# MCU.net
KiCad netlist of a schematic drawn in Altium Designer
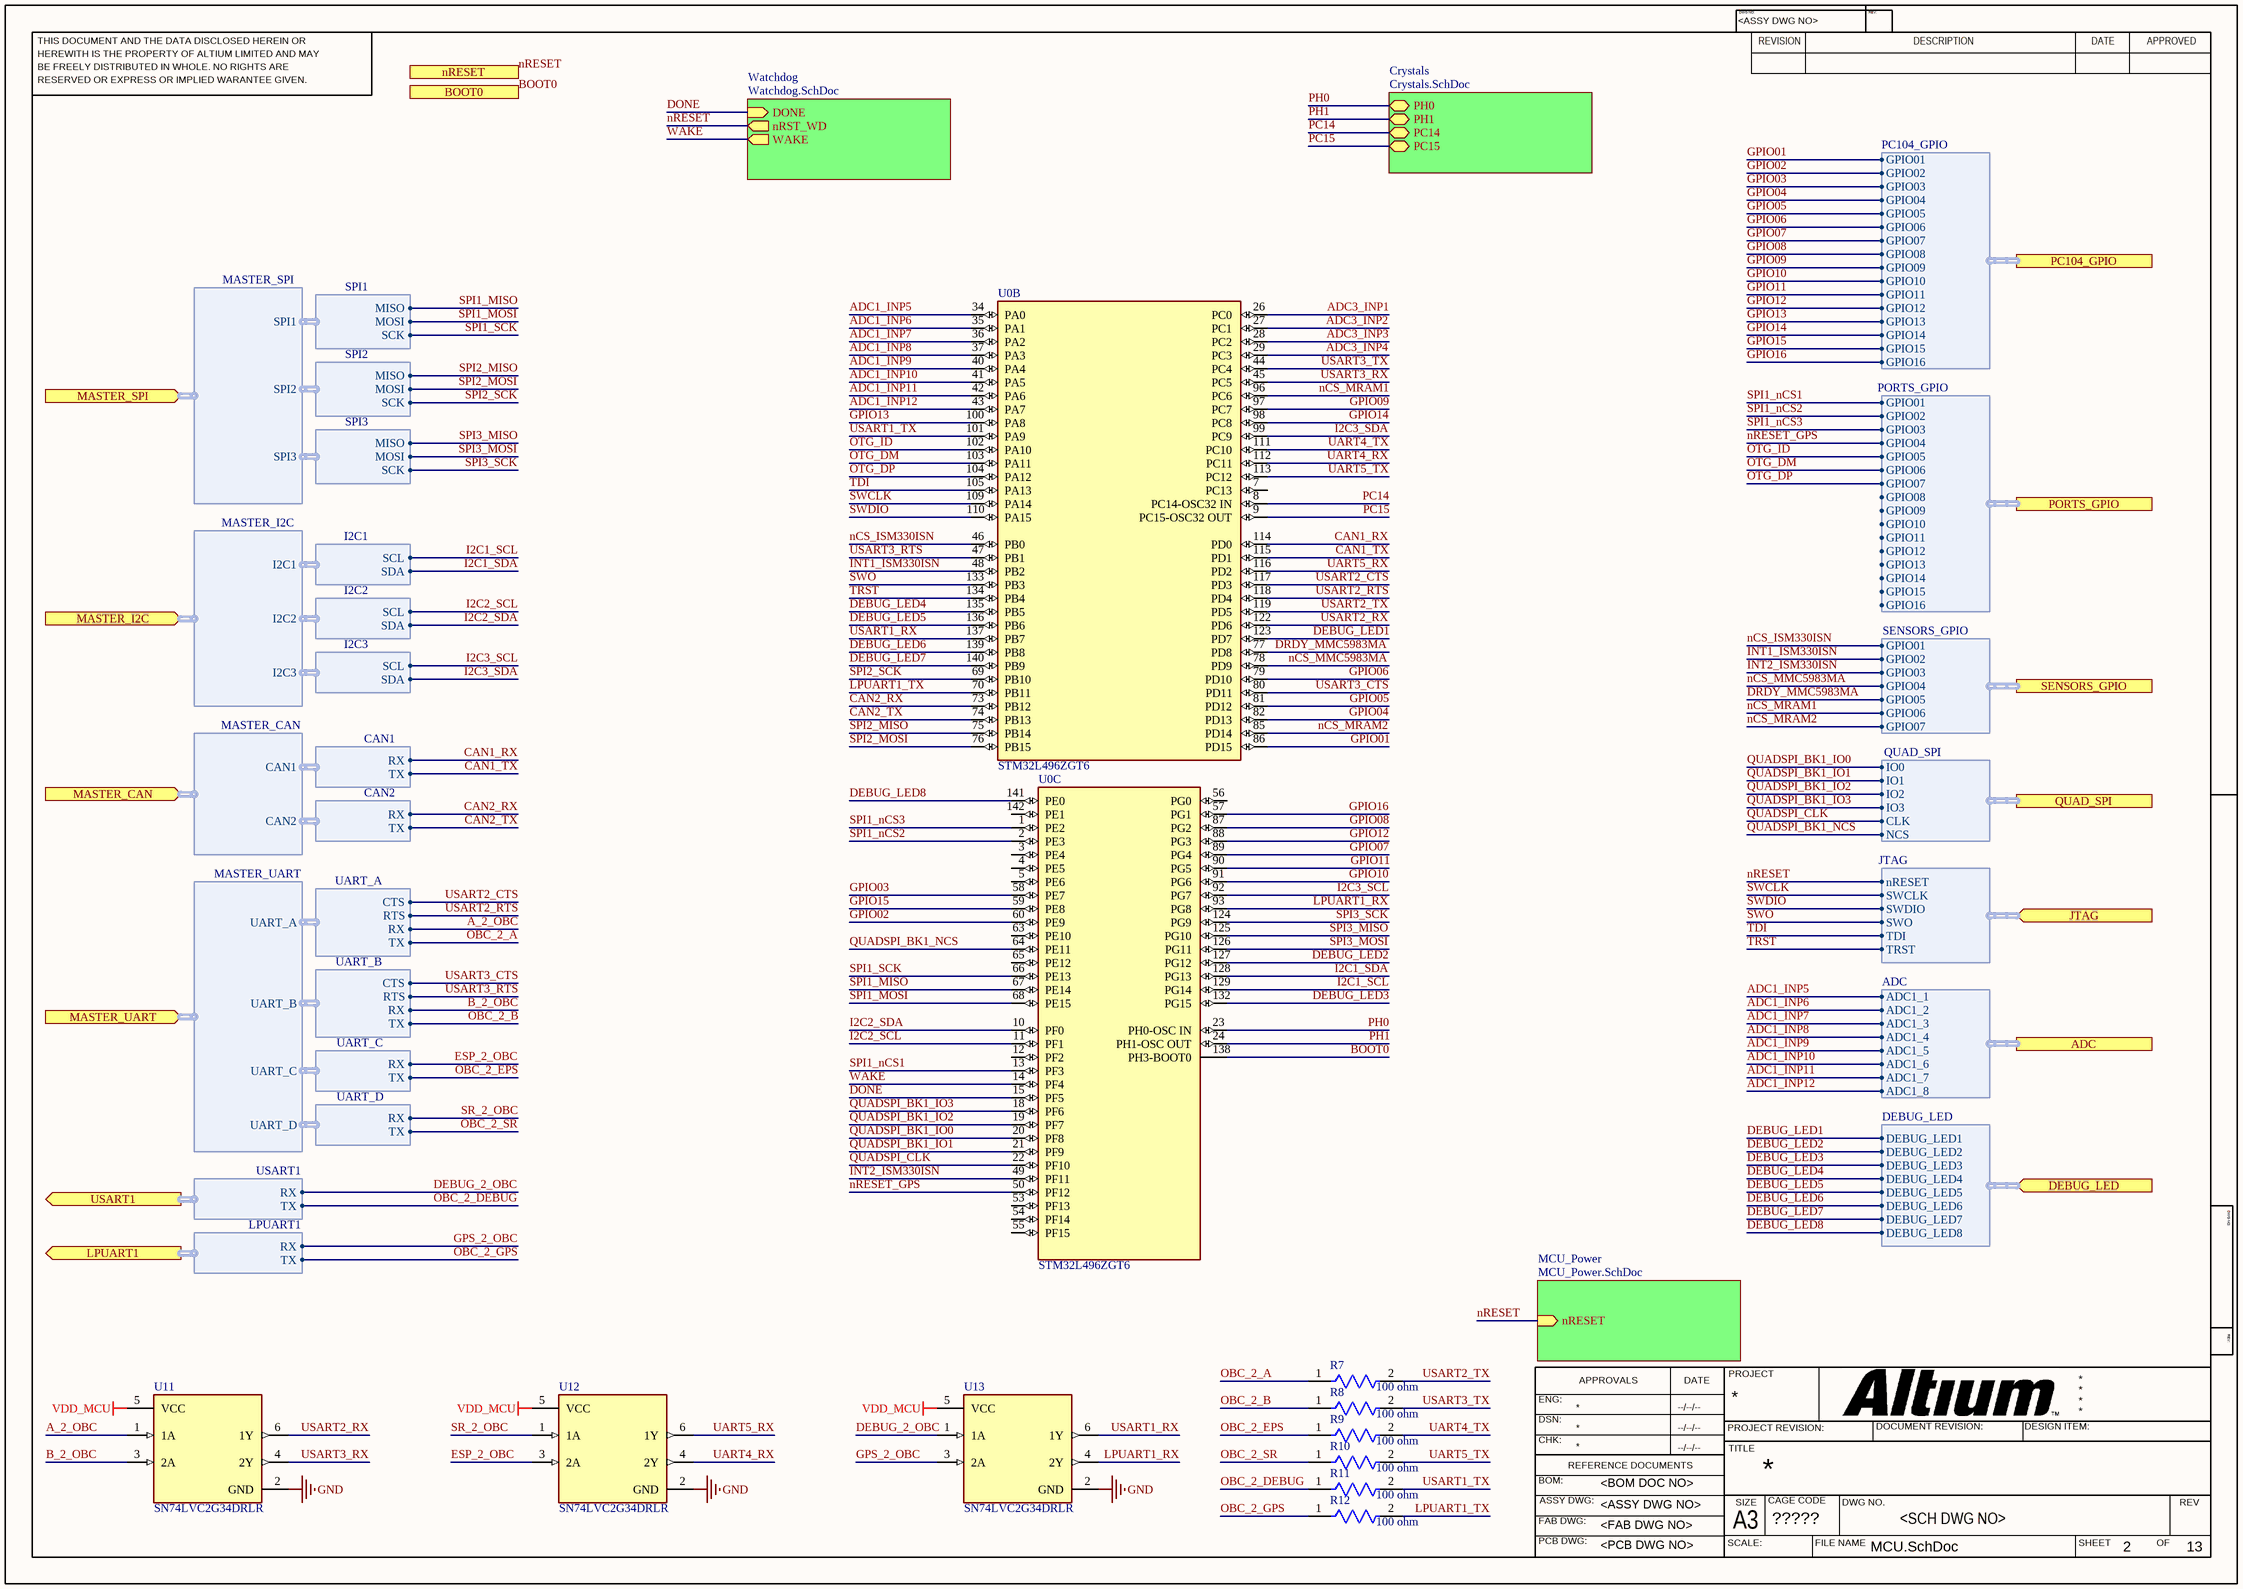
[diagram p0: MCU.SchDoc]

(export (version "E")
  (design (tool "Eeschema 10.0.6"))
  (components
    (comp (ref "R7")
      (value "100 ohm")
      (footprint "FP-ERJP03-MFG")
      (description "ERJ-P03F1000V SMD Chip Resistor, 100 Ohm, ± 1%, 200 mW, 0603 [1608 Metric], Thick Film, Anti-Surge")
      (fields (field (name "TOLERANCE") "1%"))
      (libsource (lib "Altium Content Vault") (part "1029c3af85768c4190bb7ad29bc67b5"))
    )
    (comp (ref "R8")
      (value "100 ohm")
      (footprint "FP-ERJP03-MFG")
      (description "ERJ-P03F1000V SMD Chip Resistor, 100 Ohm, ± 1%, 200 mW, 0603 [1608 Metric], Thick Film, Anti-Surge")
      (fields (field (name "TOLERANCE") "1%"))
      (libsource (lib "Altium Content Vault") (part "1029c3af85768c4190bb7ad29bc67b5"))
    )
    (comp (ref "R9")
      (value "100 ohm")
      (footprint "FP-ERJP03-MFG")
      (description "ERJ-P03F1000V SMD Chip Resistor, 100 Ohm, ± 1%, 200 mW, 0603 [1608 Metric], Thick Film, Anti-Surge")
      (fields (field (name "TOLERANCE") "1%"))
      (libsource (lib "Altium Content Vault") (part "1029c3af85768c4190bb7ad29bc67b5"))
    )
    (comp (ref "R10")
      (value "100 ohm")
      (footprint "FP-ERJP03-MFG")
      (description "ERJ-P03F1000V SMD Chip Resistor, 100 Ohm, ± 1%, 200 mW, 0603 [1608 Metric], Thick Film, Anti-Surge")
      (fields (field (name "TOLERANCE") "1%"))
      (libsource (lib "Altium Content Vault") (part "1029c3af85768c4190bb7ad29bc67b5"))
    )
    (comp (ref "R11")
      (value "100 ohm")
      (footprint "FP-ERJP03-MFG")
      (description "ERJ-P03F1000V SMD Chip Resistor, 100 Ohm, ± 1%, 200 mW, 0603 [1608 Metric], Thick Film, Anti-Surge")
      (fields (field (name "TOLERANCE") "1%"))
      (libsource (lib "Altium Content Vault") (part "1029c3af85768c4190bb7ad29bc67b5"))
    )
    (comp (ref "R12")
      (value "100 ohm")
      (footprint "FP-ERJP03-MFG")
      (description "ERJ-P03F1000V SMD Chip Resistor, 100 Ohm, ± 1%, 200 mW, 0603 [1608 Metric], Thick Film, Anti-Surge")
      (fields (field (name "TOLERANCE") "1%"))
      (libsource (lib "Altium Content Vault") (part "1029c3af85768c4190bb7ad29bc67b5"))
    )
    (comp (ref "U0")
      (value "STM32L496ZGT6")
      (footprint "FP-LQFP144-1A-MFG")
      (description "IC MCU 32BIT 1MB FLASH 144LQFP")
      (libsource (lib "Altium Content Vault") (part "f8f598a4e7bf6abd6ff1d35fb83b48f"))
    )
    (comp (ref "U11")
      (value "SN74LVC2G34DRLR")
      (footprint "FP-DRL0006A-MFG")
      (description "IC BUFFER NON-INVERT 5.5V 6SOT")
      (libsource (lib "Altium Content Vault") (part "59303bce76f5fafbc101ba271662c75"))
    )
    (comp (ref "U12")
      (value "SN74LVC2G34DRLR")
      (footprint "FP-DRL0006A-MFG")
      (description "IC BUFFER NON-INVERT 5.5V 6SOT")
      (libsource (lib "Altium Content Vault") (part "59303bce76f5fafbc101ba271662c75"))
    )
    (comp (ref "U13")
      (value "SN74LVC2G34DRLR")
      (footprint "FP-DRL0006A-MFG")
      (description "IC BUFFER NON-INVERT 5.5V 6SOT")
      (libsource (lib "Altium Content Vault") (part "59303bce76f5fafbc101ba271662c75"))
    )
  )
  (nets
    (net (code "26") (name "/ADC1_INP5") (class "Default")
      (node (ref "U0") (pin "34") (pinfunction "PA0_34") (pintype "bidirectional"))
    )
    (net (code "27") (name "/ADC1_INP6") (class "Default")
      (node (ref "U0") (pin "35") (pinfunction "PA1_35") (pintype "bidirectional"))
    )
    (net (code "28") (name "/ADC1_INP7") (class "Default")
      (node (ref "U0") (pin "36") (pinfunction "PA2_36") (pintype "bidirectional"))
    )
    (net (code "29") (name "/ADC1_INP8") (class "Default")
      (node (ref "U0") (pin "37") (pinfunction "PA3_37") (pintype "bidirectional"))
    )
    (net (code "30") (name "/ADC1_INP9") (class "Default")
      (node (ref "U0") (pin "40") (pinfunction "PA4_40") (pintype "bidirectional"))
    )
    (net (code "31") (name "/ADC1_INP10") (class "Default")
      (node (ref "U0") (pin "41") (pinfunction "PA5_41") (pintype "bidirectional"))
    )
    (net (code "32") (name "/ADC1_INP11") (class "Default")
      (node (ref "U0") (pin "42") (pinfunction "PA6_42") (pintype "bidirectional"))
    )
    (net (code "33") (name "/ADC1_INP12") (class "Default")
      (node (ref "U0") (pin "43") (pinfunction "PA7_43") (pintype "bidirectional"))
    )
    (net (code "34") (name "/ADC3_INP1") (class "Default")
      (node (ref "U0") (pin "26") (pinfunction "PC0_26") (pintype "bidirectional"))
    )
    (net (code "35") (name "/ADC3_INP2") (class "Default")
      (node (ref "U0") (pin "27") (pinfunction "PC1_27") (pintype "bidirectional"))
    )
    (net (code "36") (name "/ADC3_INP3") (class "Default")
      (node (ref "U0") (pin "28") (pinfunction "PC2_28") (pintype "bidirectional"))
    )
    (net (code "37") (name "/ADC3_INP4") (class "Default")
      (node (ref "U0") (pin "29") (pinfunction "PC3_29") (pintype "bidirectional"))
    )
    (net (code "38") (name "/A_2_OBC") (class "Default")
      (node (ref "U11") (pin "1") (pinfunction "1A_1") (pintype "input"))
    )
    (net (code "39") (name "/BOOT0") (class "Default")
      (node (ref "U0") (pin "138") (pinfunction "PH3-BOOT0_138") (pintype "passive"))
    )
    (net (code "40") (name "/B_2_OBC") (class "Default")
      (node (ref "U11") (pin "3") (pinfunction "2A_3") (pintype "input"))
    )
    (net (code "41") (name "/CAN1_RX") (class "Default")
      (node (ref "U0") (pin "114") (pinfunction "PD0_114") (pintype "bidirectional"))
    )
    (net (code "42") (name "/CAN1_TX") (class "Default")
      (node (ref "U0") (pin "115") (pinfunction "PD1_115") (pintype "bidirectional"))
    )
    (net (code "43") (name "/CAN2_RX") (class "Default")
      (node (ref "U0") (pin "73") (pinfunction "PB12_73") (pintype "bidirectional"))
    )
    (net (code "44") (name "/CAN2_TX") (class "Default")
      (node (ref "U0") (pin "74") (pinfunction "PB13_74") (pintype "bidirectional"))
    )
    (net (code "45") (name "/DEBUG_2_OBC") (class "Default")
      (node (ref "U13") (pin "1") (pinfunction "1A_1") (pintype "input"))
    )
    (net (code "46") (name "/DEBUG_LED1") (class "Default")
      (node (ref "U0") (pin "123") (pinfunction "PD7_123") (pintype "bidirectional"))
    )
    (net (code "47") (name "/DEBUG_LED2") (class "Default")
      (node (ref "U0") (pin "127") (pinfunction "PG12_127") (pintype "bidirectional"))
    )
    (net (code "48") (name "/DEBUG_LED3") (class "Default")
      (node (ref "U0") (pin "132") (pinfunction "PG15_132") (pintype "bidirectional"))
    )
    (net (code "49") (name "/DEBUG_LED4") (class "Default")
      (node (ref "U0") (pin "135") (pinfunction "PB5_135") (pintype "bidirectional"))
    )
    (net (code "50") (name "/DEBUG_LED5") (class "Default")
      (node (ref "U0") (pin "136") (pinfunction "PB6_136") (pintype "bidirectional"))
    )
    (net (code "51") (name "/DEBUG_LED6") (class "Default")
      (node (ref "U0") (pin "139") (pinfunction "PB8_139") (pintype "bidirectional"))
    )
    (net (code "52") (name "/DEBUG_LED7") (class "Default")
      (node (ref "U0") (pin "140") (pinfunction "PB9_140") (pintype "bidirectional"))
    )
    (net (code "53") (name "/DEBUG_LED8") (class "Default")
      (node (ref "U0") (pin "141") (pinfunction "PE0_141") (pintype "bidirectional"))
    )
    (net (code "54") (name "/DONE") (class "Default")
      (node (ref "U0") (pin "15") (pinfunction "PF5_15") (pintype "bidirectional"))
    )
    (net (code "55") (name "/DRDY_MMC5983MA") (class "Default")
      (node (ref "U0") (pin "77") (pinfunction "PD8_77") (pintype "bidirectional"))
    )
    (net (code "56") (name "/ESP_2_OBC") (class "Default")
      (node (ref "U12") (pin "3") (pinfunction "2A_3") (pintype "input"))
    )
    (net (code "57") (name "/GPIO01") (class "Default")
      (node (ref "U0") (pin "86") (pinfunction "PD15_86") (pintype "bidirectional"))
    )
    (net (code "58") (name "/GPIO02") (class "Default")
      (node (ref "U0") (pin "60") (pinfunction "PE9_60") (pintype "bidirectional"))
    )
    (net (code "59") (name "/GPIO03") (class "Default")
      (node (ref "U0") (pin "58") (pinfunction "PE7_58") (pintype "bidirectional"))
    )
    (net (code "60") (name "/GPIO04") (class "Default")
      (node (ref "U0") (pin "82") (pinfunction "PD13_82") (pintype "bidirectional"))
    )
    (net (code "61") (name "/GPIO05") (class "Default")
      (node (ref "U0") (pin "81") (pinfunction "PD12_81") (pintype "bidirectional"))
    )
    (net (code "62") (name "/GPIO06") (class "Default")
      (node (ref "U0") (pin "79") (pinfunction "PD10_79") (pintype "bidirectional"))
    )
    (net (code "63") (name "/GPIO07") (class "Default")
      (node (ref "U0") (pin "89") (pinfunction "PG4_89") (pintype "bidirectional"))
    )
    (net (code "64") (name "/GPIO08") (class "Default")
      (node (ref "U0") (pin "87") (pinfunction "PG2_87") (pintype "bidirectional"))
    )
    (net (code "65") (name "/GPIO09") (class "Default")
      (node (ref "U0") (pin "97") (pinfunction "PC7_97") (pintype "bidirectional"))
    )
    (net (code "66") (name "/GPIO10") (class "Default")
      (node (ref "U0") (pin "91") (pinfunction "PG6_91") (pintype "bidirectional"))
    )
    (net (code "67") (name "/GPIO11") (class "Default")
      (node (ref "U0") (pin "90") (pinfunction "PG5_90") (pintype "bidirectional"))
    )
    (net (code "68") (name "/GPIO12") (class "Default")
      (node (ref "U0") (pin "88") (pinfunction "PG3_88") (pintype "bidirectional"))
    )
    (net (code "69") (name "/GPIO13") (class "Default")
      (node (ref "U0") (pin "100") (pinfunction "PA8_100") (pintype "bidirectional"))
    )
    (net (code "70") (name "/GPIO14") (class "Default")
      (node (ref "U0") (pin "98") (pinfunction "PC8_98") (pintype "bidirectional"))
    )
    (net (code "71") (name "/GPIO15") (class "Default")
      (node (ref "U0") (pin "59") (pinfunction "PE8_59") (pintype "bidirectional"))
    )
    (net (code "72") (name "/GPIO16") (class "Default")
      (node (ref "U0") (pin "57") (pinfunction "PG1_57") (pintype "bidirectional"))
    )
    (net (code "73") (name "/GPS_2_OBC") (class "Default")
      (node (ref "U13") (pin "3") (pinfunction "2A_3") (pintype "input"))
    )
    (net (code "74") (name "/I2C1_SCL") (class "Default")
      (node (ref "U0") (pin "129") (pinfunction "PG14_129") (pintype "bidirectional"))
    )
    (net (code "75") (name "/I2C1_SDA") (class "Default")
      (node (ref "U0") (pin "128") (pinfunction "PG13_128") (pintype "bidirectional"))
    )
    (net (code "76") (name "/I2C2_SCL") (class "Default")
      (node (ref "U0") (pin "11") (pinfunction "PF1_11") (pintype "bidirectional"))
    )
    (net (code "77") (name "/I2C2_SDA") (class "Default")
      (node (ref "U0") (pin "10") (pinfunction "PF0_10") (pintype "bidirectional"))
    )
    (net (code "78") (name "/I2C3_SCL") (class "Default")
      (node (ref "U0") (pin "92") (pinfunction "PG7_92") (pintype "bidirectional"))
    )
    (net (code "79") (name "/I2C3_SDA") (class "Default")
      (node (ref "U0") (pin "99") (pinfunction "PC9_99") (pintype "bidirectional"))
    )
    (net (code "80") (name "/INT1_ISM330ISN") (class "Default")
      (node (ref "U0") (pin "48") (pinfunction "PB2_48") (pintype "bidirectional"))
    )
    (net (code "81") (name "/INT2_ISM330ISN") (class "Default")
      (node (ref "U0") (pin "49") (pinfunction "PF11_49") (pintype "bidirectional"))
    )
    (net (code "82") (name "/LPUART1_RX") (class "Default")
      (node (ref "U0") (pin "93") (pinfunction "PG8_93") (pintype "bidirectional"))
      (node (ref "U13") (pin "4") (pinfunction "2Y_4") (pintype "output"))
    )
    (net (code "83") (name "/LPUART1_TX") (class "Default")
      (node (ref "R12") (pin "2") (pinfunction "2_2") (pintype "passive"))
      (node (ref "U0") (pin "70") (pinfunction "PB11_70") (pintype "bidirectional"))
    )
    (net (code "88") (name "/OBC_2_A") (class "Default")
      (node (ref "R7") (pin "1") (pinfunction "1_1") (pintype "passive"))
    )
    (net (code "89") (name "/OBC_2_B") (class "Default")
      (node (ref "R8") (pin "1") (pinfunction "1_1") (pintype "passive"))
    )
    (net (code "90") (name "/OBC_2_DEBUG") (class "Default")
      (node (ref "R11") (pin "1") (pinfunction "1_1") (pintype "passive"))
    )
    (net (code "91") (name "/OBC_2_EPS") (class "Default")
      (node (ref "R9") (pin "1") (pinfunction "1_1") (pintype "passive"))
    )
    (net (code "92") (name "/OBC_2_GPS") (class "Default")
      (node (ref "R12") (pin "1") (pinfunction "1_1") (pintype "passive"))
    )
    (net (code "93") (name "/OBC_2_SR") (class "Default")
      (node (ref "R10") (pin "1") (pinfunction "1_1") (pintype "passive"))
    )
    (net (code "94") (name "/OTG_DM") (class "Default")
      (node (ref "U0") (pin "103") (pinfunction "PA11_103") (pintype "bidirectional"))
    )
    (net (code "95") (name "/OTG_DP") (class "Default")
      (node (ref "U0") (pin "104") (pinfunction "PA12_104") (pintype "bidirectional"))
    )
    (net (code "96") (name "/OTG_ID") (class "Default")
      (node (ref "U0") (pin "102") (pinfunction "PA10_102") (pintype "bidirectional"))
    )
    (net (code "97") (name "/PC14") (class "Default")
      (node (ref "U0") (pin "8") (pinfunction "PC14-OSC32_IN_8") (pintype "bidirectional"))
    )
    (net (code "98") (name "/PC15") (class "Default")
      (node (ref "U0") (pin "9") (pinfunction "PC15-OSC32_OUT_9") (pintype "bidirectional"))
    )
    (net (code "99") (name "/PH0") (class "Default")
      (node (ref "U0") (pin "23") (pinfunction "PH0-OSC_IN_23") (pintype "bidirectional"))
    )
    (net (code "100") (name "/PH1") (class "Default")
      (node (ref "U0") (pin "24") (pinfunction "PH1-OSC_OUT_24") (pintype "bidirectional"))
    )
    (net (code "101") (name "/QUADSPI_BK1_IO0") (class "Default")
      (node (ref "U0") (pin "20") (pinfunction "PF8_20") (pintype "bidirectional"))
    )
    (net (code "102") (name "/QUADSPI_BK1_IO1") (class "Default")
      (node (ref "U0") (pin "21") (pinfunction "PF9_21") (pintype "bidirectional"))
    )
    (net (code "103") (name "/QUADSPI_BK1_IO2") (class "Default")
      (node (ref "U0") (pin "19") (pinfunction "PF7_19") (pintype "bidirectional"))
    )
    (net (code "104") (name "/QUADSPI_BK1_IO3") (class "Default")
      (node (ref "U0") (pin "18") (pinfunction "PF6_18") (pintype "bidirectional"))
    )
    (net (code "105") (name "/QUADSPI_BK1_NCS") (class "Default")
      (node (ref "U0") (pin "64") (pinfunction "PE11_64") (pintype "bidirectional"))
    )
    (net (code "106") (name "/QUADSPI_CLK") (class "Default")
      (node (ref "U0") (pin "22") (pinfunction "PF10_22") (pintype "bidirectional"))
    )
    (net (code "107") (name "/SPI1_MISO") (class "Default")
      (node (ref "U0") (pin "67") (pinfunction "PE14_67") (pintype "bidirectional"))
    )
    (net (code "108") (name "/SPI1_MOSI") (class "Default")
      (node (ref "U0") (pin "68") (pinfunction "PE15_68") (pintype "bidirectional"))
    )
    (net (code "109") (name "/SPI1_SCK") (class "Default")
      (node (ref "U0") (pin "66") (pinfunction "PE13_66") (pintype "bidirectional"))
    )
    (net (code "110") (name "/SPI1_nCS1") (class "Default")
      (node (ref "U0") (pin "13") (pinfunction "PF3_13") (pintype "bidirectional"))
    )
    (net (code "111") (name "/SPI1_nCS2") (class "Default")
      (node (ref "U0") (pin "2") (pinfunction "PE3_2") (pintype "bidirectional"))
    )
    (net (code "112") (name "/SPI1_nCS3") (class "Default")
      (node (ref "U0") (pin "1") (pinfunction "PE2_1") (pintype "bidirectional"))
    )
    (net (code "113") (name "/SPI2_MISO") (class "Default")
      (node (ref "U0") (pin "75") (pinfunction "PB14_75") (pintype "bidirectional"))
    )
    (net (code "114") (name "/SPI2_MOSI") (class "Default")
      (node (ref "U0") (pin "76") (pinfunction "PB15_76") (pintype "bidirectional"))
    )
    (net (code "115") (name "/SPI2_SCK") (class "Default")
      (node (ref "U0") (pin "69") (pinfunction "PB10_69") (pintype "bidirectional"))
    )
    (net (code "116") (name "/SPI3_MISO") (class "Default")
      (node (ref "U0") (pin "125") (pinfunction "PG10_125") (pintype "bidirectional"))
    )
    (net (code "117") (name "/SPI3_MOSI") (class "Default")
      (node (ref "U0") (pin "126") (pinfunction "PG11_126") (pintype "bidirectional"))
    )
    (net (code "118") (name "/SPI3_SCK") (class "Default")
      (node (ref "U0") (pin "124") (pinfunction "PG9_124") (pintype "bidirectional"))
    )
    (net (code "119") (name "/SR_2_OBC") (class "Default")
      (node (ref "U12") (pin "1") (pinfunction "1A_1") (pintype "input"))
    )
    (net (code "120") (name "/SWCLK") (class "Default")
      (node (ref "U0") (pin "109") (pinfunction "PA14_109") (pintype "bidirectional"))
    )
    (net (code "121") (name "/SWDIO") (class "Default")
      (node (ref "U0") (pin "110") (pinfunction "PA15_110") (pintype "bidirectional"))
    )
    (net (code "122") (name "/SWO") (class "Default")
      (node (ref "U0") (pin "133") (pinfunction "PB3_133") (pintype "bidirectional"))
    )
    (net (code "123") (name "/TDI") (class "Default")
      (node (ref "U0") (pin "105") (pinfunction "PA13_105") (pintype "bidirectional"))
    )
    (net (code "124") (name "/TRST") (class "Default")
      (node (ref "U0") (pin "134") (pinfunction "PB4_134") (pintype "bidirectional"))
    )
    (net (code "125") (name "/UART4_RX") (class "Default")
      (node (ref "U0") (pin "112") (pinfunction "PC11_112") (pintype "bidirectional"))
      (node (ref "U12") (pin "4") (pinfunction "2Y_4") (pintype "output"))
    )
    (net (code "126") (name "/UART4_TX") (class "Default")
      (node (ref "R9") (pin "2") (pinfunction "2_2") (pintype "passive"))
      (node (ref "U0") (pin "111") (pinfunction "PC10_111") (pintype "bidirectional"))
    )
    (net (code "127") (name "/UART5_RX") (class "Default")
      (node (ref "U0") (pin "116") (pinfunction "PD2_116") (pintype "bidirectional"))
      (node (ref "U12") (pin "6") (pinfunction "1Y_6") (pintype "output"))
    )
    (net (code "128") (name "/UART5_TX") (class "Default")
      (node (ref "R10") (pin "2") (pinfunction "2_2") (pintype "passive"))
      (node (ref "U0") (pin "113") (pinfunction "PC12_113") (pintype "bidirectional"))
    )
    (net (code "129") (name "/USART1_RX") (class "Default")
      (node (ref "U0") (pin "137") (pinfunction "PB7_137") (pintype "bidirectional"))
      (node (ref "U13") (pin "6") (pinfunction "1Y_6") (pintype "output"))
    )
    (net (code "130") (name "/USART1_TX") (class "Default")
      (node (ref "R11") (pin "2") (pinfunction "2_2") (pintype "passive"))
      (node (ref "U0") (pin "101") (pinfunction "PA9_101") (pintype "bidirectional"))
    )
    (net (code "131") (name "/USART2_CTS") (class "Default")
      (node (ref "U0") (pin "117") (pinfunction "PD3_117") (pintype "bidirectional"))
    )
    (net (code "132") (name "/USART2_RTS") (class "Default")
      (node (ref "U0") (pin "118") (pinfunction "PD4_118") (pintype "bidirectional"))
    )
    (net (code "133") (name "/USART2_RX") (class "Default")
      (node (ref "U0") (pin "122") (pinfunction "PD6_122") (pintype "bidirectional"))
      (node (ref "U11") (pin "6") (pinfunction "1Y_6") (pintype "output"))
    )
    (net (code "134") (name "/USART2_TX") (class "Default")
      (node (ref "R7") (pin "2") (pinfunction "2_2") (pintype "passive"))
      (node (ref "U0") (pin "119") (pinfunction "PD5_119") (pintype "bidirectional"))
    )
    (net (code "135") (name "/USART3_CTS") (class "Default")
      (node (ref "U0") (pin "80") (pinfunction "PD11_80") (pintype "bidirectional"))
    )
    (net (code "136") (name "/USART3_RTS") (class "Default")
      (node (ref "U0") (pin "47") (pinfunction "PB1_47") (pintype "bidirectional"))
    )
    (net (code "137") (name "/USART3_RX") (class "Default")
      (node (ref "U0") (pin "45") (pinfunction "PC5_45") (pintype "bidirectional"))
      (node (ref "U11") (pin "4") (pinfunction "2Y_4") (pintype "output"))
    )
    (net (code "138") (name "/USART3_TX") (class "Default")
      (node (ref "R8") (pin "2") (pinfunction "2_2") (pintype "passive"))
      (node (ref "U0") (pin "44") (pinfunction "PC4_44") (pintype "bidirectional"))
    )
    (net (code "139") (name "/WAKE") (class "Default")
      (node (ref "U0") (pin "14") (pinfunction "PF4_14") (pintype "bidirectional"))
    )
    (net (code "140") (name "/nCS_ISM330ISN") (class "Default")
      (node (ref "U0") (pin "46") (pinfunction "PB0_46") (pintype "bidirectional"))
    )
    (net (code "141") (name "/nCS_MMC5983MA") (class "Default")
      (node (ref "U0") (pin "78") (pinfunction "PD9_78") (pintype "bidirectional"))
    )
    (net (code "142") (name "/nCS_MRAM1") (class "Default")
      (node (ref "U0") (pin "96") (pinfunction "PC6_96") (pintype "bidirectional"))
    )
    (net (code "143") (name "/nCS_MRAM2") (class "Default")
      (node (ref "U0") (pin "85") (pinfunction "PD14_85") (pintype "bidirectional"))
    )
    (net (code "145") (name "/nRESET_GPS") (class "Default")
      (node (ref "U0") (pin "50") (pinfunction "PF12_50") (pintype "bidirectional"))
    )
    (net (code "167") (name "GND") (class "Default")
      (node (ref "U11") (pin "2") (pinfunction "GND_2") (pintype "power_in"))
      (node (ref "U12") (pin "2") (pinfunction "GND_2") (pintype "power_in"))
      (node (ref "U13") (pin "2") (pinfunction "GND_2") (pintype "power_in"))
    )
    (net (code "168") (name "VDD_MCU") (class "Default")
      (node (ref "U11") (pin "5") (pinfunction "VCC_5") (pintype "power_in"))
      (node (ref "U12") (pin "5") (pinfunction "VCC_5") (pintype "power_in"))
      (node (ref "U13") (pin "5") (pinfunction "VCC_5") (pintype "power_in"))
    )
    (net (code "169") (name "unconnected-(U0B-PC13-Pad7)") (class "Default")
      (node (ref "U0") (pin "7") (pinfunction "PC13_7") (pintype "bidirectional"))
    )
    (net (code "170") (name "unconnected-(U0C-PE1-Pad142)") (class "Default")
      (node (ref "U0") (pin "142") (pinfunction "PE1_142") (pintype "bidirectional"))
    )
    (net (code "171") (name "unconnected-(U0C-PE4-Pad3)") (class "Default")
      (node (ref "U0") (pin "3") (pinfunction "PE4_3") (pintype "bidirectional"))
    )
    (net (code "172") (name "unconnected-(U0C-PE5-Pad4)") (class "Default")
      (node (ref "U0") (pin "4") (pinfunction "PE5_4") (pintype "bidirectional"))
    )
    (net (code "173") (name "unconnected-(U0C-PE6-Pad5)") (class "Default")
      (node (ref "U0") (pin "5") (pinfunction "PE6_5") (pintype "bidirectional"))
    )
    (net (code "174") (name "unconnected-(U0C-PE10-Pad63)") (class "Default")
      (node (ref "U0") (pin "63") (pinfunction "PE10_63") (pintype "bidirectional"))
    )
    (net (code "175") (name "unconnected-(U0C-PE12-Pad65)") (class "Default")
      (node (ref "U0") (pin "65") (pinfunction "PE12_65") (pintype "bidirectional"))
    )
    (net (code "176") (name "unconnected-(U0C-PF2-Pad12)") (class "Default")
      (node (ref "U0") (pin "12") (pinfunction "PF2_12") (pintype "bidirectional"))
    )
    (net (code "177") (name "unconnected-(U0C-PF13-Pad53)") (class "Default")
      (node (ref "U0") (pin "53") (pinfunction "PF13_53") (pintype "bidirectional"))
    )
    (net (code "178") (name "unconnected-(U0C-PF14-Pad54)") (class "Default")
      (node (ref "U0") (pin "54") (pinfunction "PF14_54") (pintype "bidirectional"))
    )
    (net (code "179") (name "unconnected-(U0C-PF15-Pad55)") (class "Default")
      (node (ref "U0") (pin "55") (pinfunction "PF15_55") (pintype "bidirectional"))
    )
    (net (code "180") (name "unconnected-(U0C-PG0-Pad56)") (class "Default")
      (node (ref "U0") (pin "56") (pinfunction "PG0_56") (pintype "bidirectional"))
    )
  )
)
